# DM0255_Power.net
KiCad netlist of a schematic drawn in Altium Designer
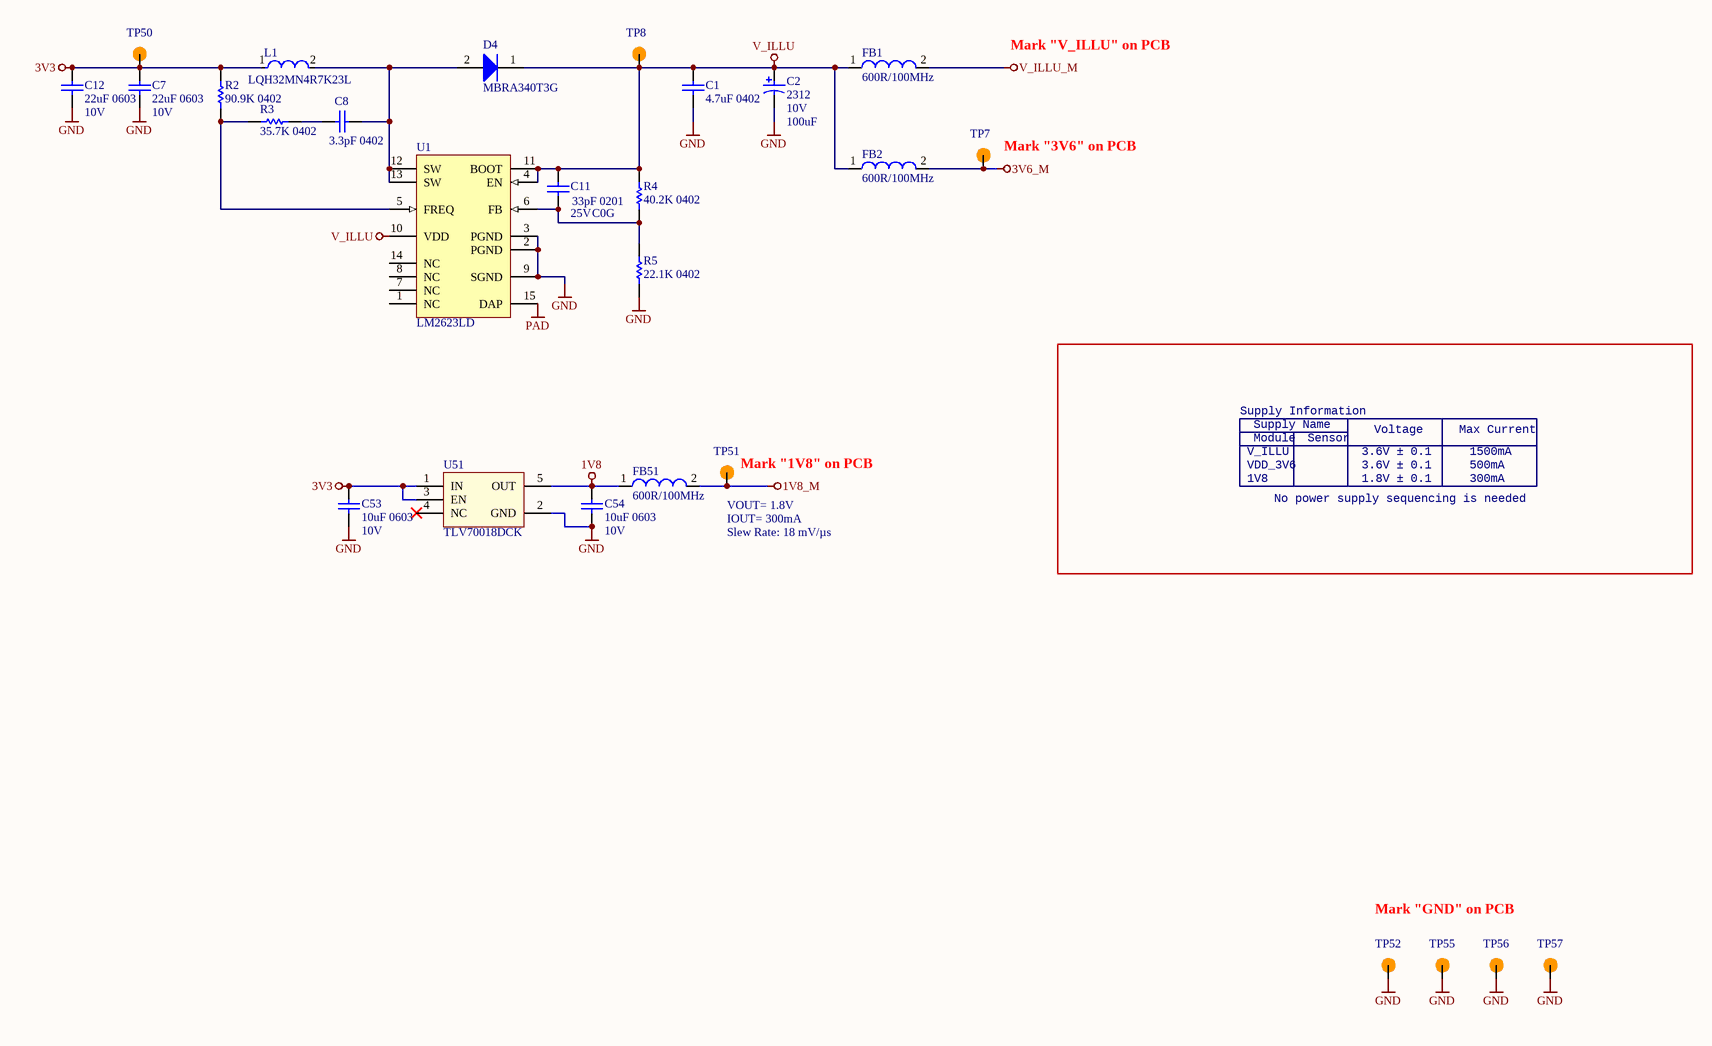
[diagram p0: DM0255_Power.SchDoc]

(export (version "E")
  (design (tool "Eeschema 10.0.6"))
  (components
    (comp (ref "C1")
      (value "4.7uF 0402")
      (footprint "CAP_Altium_Vault_Generic:CAPC0402(1005)70_N")
      (description "CAP CER 4.7UF 6.3V X5R 0402")
      (fields (field (name "TOLERANCE") "20%") (field (name "VOLTAGE") "6.3V"))
      (libsource (lib "LuxonisMaster") (part "GRM155R60J475ME87D"))
    )
    (comp (ref "C2")
      (value "TAJC107K010RNJ")
      (footprint "AVX-TAJ-C-2_L")
      (fields
        (field (name "SIZE CODE") "2312")
        (field (name "RATED DC VOLTAGE (URDC)") "10V")
        (field (name "CAPACITANCE") "100uF")
      )
      (libsource (lib "DM0255") (part "TAJC107K010RNJ"))
    )
    (comp (ref "C7")
      (value "22uF 0603")
      (footprint "CAP_Altium_Vault_Generic:CAPC0603(1608)100_N")
      (description "CAP CER 22UF 10V X5R 0603 20%")
      (fields (field (name "TOLERANCE") "20%") (field (name "VOLTAGE RATING") "10V"))
      (libsource (lib "LuxonisMaster") (part "GRM188R61A226ME15D"))
    )
    (comp (ref "C8")
      (value "3.3pF 0402")
      (footprint "CAP_Altium_Vault_Generic:CAPC0402(1005)60_L")
      (libsource (lib "LuxonisMaster") (part "GRM1555C1H3R3BA01D"))
    )
    (comp (ref "C11")
      (value "33pF 0201")
      (footprint "CAP_Altium_Vault_Generic:CAPC0201(0603)33_L")
      (description "CAP CER 33PF 25V C0G/NP0 0201")
      (fields
        (field (name "TOLERANCE") "5%")
        (field (name "VOLTAGE RATING") "25V")
        (field (name "DIELECTRIC") "C0G")
      )
      (libsource (lib "LuxonisMaster") (part "GRM0335C1E330JA01D"))
    )
    (comp (ref "C12")
      (value "22uF 0603")
      (footprint "CAP_Altium_Vault_Generic:CAPC0603(1608)100_N")
      (description "CAP CER 22UF 10V X5R 0603 20%")
      (fields (field (name "TOLERANCE") "20%") (field (name "VOLTAGE RATING") "10V"))
      (libsource (lib "LuxonisMaster") (part "GRM188R61A226ME15D"))
    )
    (comp (ref "C53")
      (value "10uF 0603")
      (footprint "CAP_Altium_Vault_Generic:CAPC0603(1608)100_N")
      (description "CAP CER 10UF 10V X5R 0603 20%")
      (fields (field (name "TOLERANCE") "20%") (field (name "VOLTAGE RATING") "10V"))
      (libsource (lib "LuxonisMaster") (part "GRM188R61A106ME69D"))
    )
    (comp (ref "C54")
      (value "10uF 0603")
      (footprint "CAP_Altium_Vault_Generic:CAPC0603(1608)100_N")
      (description "CAP CER 10UF 10V X5R 0603 20%")
      (fields (field (name "TOLERANCE") "20%") (field (name "VOLTAGE RATING") "10V"))
      (libsource (lib "LuxonisMaster") (part "GRM188R61A106ME69D"))
    )
    (comp (ref "D4")
      (value "MBRA340T3G")
      (footprint "DM0255:ONSC-SMA-2-403D-02_F_V")
      (description "Schottky Power Rectifier, 2-Pin SMA, Pb-Free, Tape and Reel")
      (libsource (lib "DM0255") (part "MBRA340T3G"))
    )
    (comp (ref "FB1")
      (value "600R/100MHz")
      (footprint "LuxonisMaster:2508056017Y2")
      (description "FERRITE BEAD, 0.1OHM, 2A, 0805, 600R/100MHz")
      (fields (field (name "TOLERANCE") "25%"))
      (libsource (lib "LuxonisMaster") (part "2508056017Y2"))
    )
    (comp (ref "FB2")
      (value "600R/100MHz")
      (footprint "LuxonisMaster:2508056017Y2")
      (description "FERRITE BEAD, 0.1OHM, 2A, 0805, 600R/100MHz")
      (fields (field (name "TOLERANCE") "25%"))
      (libsource (lib "LuxonisMaster") (part "2508056017Y2"))
    )
    (comp (ref "FB51")
      (value "600R/100MHz")
      (footprint "LuxonisMaster:2508056017Y2")
      (description "FERRITE BEAD, 0.1OHM, 2A, 0805, 600R/100MHz")
      (fields (field (name "TOLERANCE") "25%"))
      (libsource (lib "LuxonisMaster") (part "2508056017Y2"))
    )
    (comp (ref "L1")
      (value "LQH32MN4R7K23L")
      (footprint "DM0255:FP-LQH32CH_23-MFG")
      (description "Wire Wound Ferrite Inductor for General Circuits 4.7μH ±10% 1.2Ω 270mA 1210")
      (fields (field (name "TOLERANCE") "10%"))
      (libsource (lib "DM0255") (part "LQH32MN4R7K23L"))
    )
    (comp (ref "R2")
      (value "90.9K 0402")
      (footprint "RES_Altium_Vault_Generic:RESC0402(1005)_L")
      (fields (field (name "TOLERANCE") "1%"))
      (libsource (lib "LuxonisMaster") (part "CRCW040290K9FKED"))
    )
    (comp (ref "R3")
      (value "35.7K 0402")
      (footprint "RES_Altium_Vault_Generic:RESC0402(1005)_L")
      (fields (field (name "TOLERANCE") "1%"))
      (libsource (lib "LuxonisMaster") (part "CRCW040235K7FKED"))
    )
    (comp (ref "R4")
      (value "40.2K 0402")
      (footprint "RES_Altium_Vault_Generic:RESC0402(1005)_L")
      (description "RES SMD 40.2K OHM 1% 1/16W 0402")
      (fields (field (name "TOLERANCE") "1%"))
      (libsource (lib "LuxonisMaster") (part "RC0402FR-0740K2L"))
    )
    (comp (ref "R5")
      (value "22.1K 0402")
      (footprint "RES_Altium_Vault_Generic:RESC0402(1005)_N")
      (description "RES SMD 22.1K OHM 1% 1/16W 0402")
      (fields (field (name "TOLERANCE") "1%"))
      (libsource (lib "LuxonisMaster") (part "RC0402FR-0722K1L"))
    )
    (comp (ref "TP7")
      (value "TP100_150_NS")
      (footprint "LuxonisMaster:TP100_150_NS")
      (libsource (lib "LuxonisMaster") (part "TEST_POINT"))
    )
    (comp (ref "TP8")
      (value "TP100_150_NS")
      (footprint "LuxonisMaster:TP100_150_NS")
      (libsource (lib "LuxonisMaster") (part "TEST_POINT"))
    )
    (comp (ref "TP50")
      (value "TP100_150_NS")
      (footprint "LuxonisMaster:TP100_150_NS")
      (libsource (lib "LuxonisMaster") (part "TEST_POINT"))
    )
    (comp (ref "TP51")
      (value "TP100_150_NS")
      (footprint "LuxonisMaster:TP100_150_NS")
      (libsource (lib "LuxonisMaster") (part "TEST_POINT"))
    )
    (comp (ref "TP52")
      (value "TP100_150_NS")
      (footprint "LuxonisMaster:TP100_150_NS")
      (libsource (lib "LuxonisMaster") (part "TEST_POINT"))
    )
    (comp (ref "TP55")
      (value "TP100_150_NS")
      (footprint "LuxonisMaster:TP100_150_NS")
      (libsource (lib "LuxonisMaster") (part "TEST_POINT"))
    )
    (comp (ref "TP56")
      (value "TP100_150_NS")
      (footprint "LuxonisMaster:TP100_150_NS")
      (libsource (lib "LuxonisMaster") (part "TEST_POINT"))
    )
    (comp (ref "TP57")
      (value "TP100_150_NS")
      (footprint "LuxonisMaster:TP100_150_NS")
      (libsource (lib "LuxonisMaster") (part "TEST_POINT"))
    )
    (comp (ref "U1")
      (value "LM2623LD")
      (footprint "DM0255:LDA14A")
      (description "General Purpose, Gated Oscillator Based, DC/DC Boost Converter, 14-pin LLP")
      (fields (field (name "MANUFACTURER") "National Semiconductor"))
      (libsource (lib "DM0255") (part "LM2623LD"))
    )
    (comp (ref "U51")
      (value "TLV70018DCK")
      (footprint "LuxonisMaster:TLV70018DCK")
      (description "IC REG LINEAR 1.8V 200MA SC70-5 Linear Voltage Regulator IC  1 Output  200mA SC-70-5")
      (libsource (lib "LuxonisMaster") (part "TLV70018DCK"))
    )
  )
  (nets
    (net (code "1") (name "1V8") (class "Default")
      (node (ref "C54") (pin "2") (pinfunction "2_2") (pintype "passive"))
      (node (ref "FB51") (pin "1") (pinfunction "1_1") (pintype "passive"))
      (node (ref "U51") (pin "5") (pinfunction "OUT_5") (pintype "passive"))
    )
    (net (code "2") (name "1V8_M") (class "Default")
      (node (ref "FB51") (pin "2") (pinfunction "2_2") (pintype "passive"))
      (node (ref "TP51") (pin "1") (pintype "passive"))
    )
    (net (code "3") (name "3V3") (class "Default")
      (node (ref "C12") (pin "2") (pinfunction "2_2") (pintype "passive"))
      (node (ref "C53") (pin "2") (pinfunction "2_2") (pintype "passive"))
      (node (ref "C7") (pin "2") (pinfunction "2_2") (pintype "passive"))
      (node (ref "L1") (pin "1") (pinfunction "1_1") (pintype "passive"))
      (node (ref "R2") (pin "2") (pinfunction "2_2") (pintype "passive"))
      (node (ref "TP50") (pin "1") (pintype "passive"))
      (node (ref "U51") (pin "1") (pinfunction "IN_1") (pintype "passive"))
      (node (ref "U51") (pin "3") (pinfunction "EN_3") (pintype "passive"))
    )
    (net (code "4") (name "3V6_M") (class "Default")
      (node (ref "FB2") (pin "2") (pinfunction "2_2") (pintype "passive"))
      (node (ref "TP7") (pin "1") (pintype "passive"))
    )
    (net (code "5") (name "GND") (class "Default")
      (node (ref "C1") (pin "1") (pinfunction "1_1") (pintype "passive"))
      (node (ref "C12") (pin "1") (pinfunction "1_1") (pintype "passive"))
      (node (ref "C2") (pin "2") (pinfunction "2_2") (pintype "passive"))
      (node (ref "C53") (pin "1") (pinfunction "1_1") (pintype "passive"))
      (node (ref "C54") (pin "1") (pinfunction "1_1") (pintype "passive"))
      (node (ref "C7") (pin "1") (pinfunction "1_1") (pintype "passive"))
      (node (ref "R5") (pin "1") (pinfunction "1_1") (pintype "passive"))
      (node (ref "TP52") (pin "1") (pintype "passive"))
      (node (ref "TP55") (pin "1") (pintype "passive"))
      (node (ref "TP56") (pin "1") (pintype "passive"))
      (node (ref "TP57") (pin "1") (pintype "passive"))
      (node (ref "U1") (pin "2") (pinfunction "PGND_2") (pintype "power_in"))
      (node (ref "U1") (pin "3") (pinfunction "PGND_3") (pintype "power_in"))
      (node (ref "U1") (pin "9") (pinfunction "SGND_9") (pintype "power_in"))
      (node (ref "U51") (pin "2") (pinfunction "GND_2") (pintype "passive"))
    )
    (net (code "6") (name "Net-(C8-Pad1)") (class "Default")
      (node (ref "C8") (pin "1") (pinfunction "1_1") (pintype "passive"))
      (node (ref "R3") (pin "2") (pinfunction "2_2") (pintype "passive"))
    )
    (net (code "7") (name "Net-(D4-A)") (class "Default")
      (node (ref "C8") (pin "2") (pinfunction "2_2") (pintype "passive"))
      (node (ref "D4") (pin "2") (pinfunction "A_2") (pintype "passive"))
      (node (ref "L1") (pin "2") (pinfunction "2_2") (pintype "passive"))
      (node (ref "U1") (pin "12") (pinfunction "SW_12") (pintype "open_collector"))
      (node (ref "U1") (pin "13") (pinfunction "SW_13") (pintype "open_collector"))
    )
    (net (code "8") (name "Net-(U1-FB)") (class "Default")
      (node (ref "C11") (pin "1") (pinfunction "1_1") (pintype "passive"))
      (node (ref "R4") (pin "1") (pinfunction "1_1") (pintype "passive"))
      (node (ref "R5") (pin "2") (pinfunction "2_2") (pintype "passive"))
      (node (ref "U1") (pin "6") (pinfunction "FB_6") (pintype "input"))
    )
    (net (code "9") (name "Net-(U1-FREQ)") (class "Default")
      (node (ref "R2") (pin "1") (pinfunction "1_1") (pintype "passive"))
      (node (ref "R3") (pin "1") (pinfunction "1_1") (pintype "passive"))
      (node (ref "U1") (pin "5") (pinfunction "FREQ_5") (pintype "input"))
    )
    (net (code "10") (name "PAD") (class "Default")
      (node (ref "U1") (pin "15") (pinfunction "DAP_15") (pintype "power_in"))
    )
    (net (code "11") (name "V_ILLU") (class "Default")
      (node (ref "C1") (pin "2") (pinfunction "2_2") (pintype "passive"))
      (node (ref "C11") (pin "2") (pinfunction "2_2") (pintype "passive"))
      (node (ref "C2") (pin "1") (pinfunction "1_1") (pintype "passive"))
      (node (ref "D4") (pin "1") (pinfunction "K_1") (pintype "passive"))
      (node (ref "FB1") (pin "1") (pinfunction "1_1") (pintype "passive"))
      (node (ref "FB2") (pin "1") (pinfunction "1_1") (pintype "passive"))
      (node (ref "R4") (pin "2") (pinfunction "2_2") (pintype "passive"))
      (node (ref "TP8") (pin "1") (pintype "passive"))
      (node (ref "U1") (pin "10") (pinfunction "VDD_10") (pintype "power_in"))
      (node (ref "U1") (pin "11") (pinfunction "BOOT_11") (pintype "passive"))
      (node (ref "U1") (pin "4") (pinfunction "EN_4") (pintype "input"))
    )
    (net (code "12") (name "V_ILLU_M") (class "Default")
      (node (ref "FB1") (pin "2") (pinfunction "2_2") (pintype "passive"))
    )
    (net (code "13") (name "unconnected-(U1-NC-Pad1)") (class "Default")
      (node (ref "U1") (pin "1") (pinfunction "NC_1") (pintype "passive"))
    )
    (net (code "14") (name "unconnected-(U1-NC-Pad7)") (class "Default")
      (node (ref "U1") (pin "7") (pinfunction "NC_7") (pintype "passive"))
    )
    (net (code "15") (name "unconnected-(U1-NC-Pad8)") (class "Default")
      (node (ref "U1") (pin "8") (pinfunction "NC_8") (pintype "passive"))
    )
    (net (code "16") (name "unconnected-(U1-NC-Pad14)") (class "Default")
      (node (ref "U1") (pin "14") (pinfunction "NC_14") (pintype "passive"))
    )
    (net (code "17") (name "unconnected-(U51-NC-Pad4)") (class "Default")
      (node (ref "U51") (pin "4") (pinfunction "NC_4") (pintype "passive+no_connect"))
    )
  )
)
